# schema.net
KiCad netlist of a schematic drawn in EAGLE
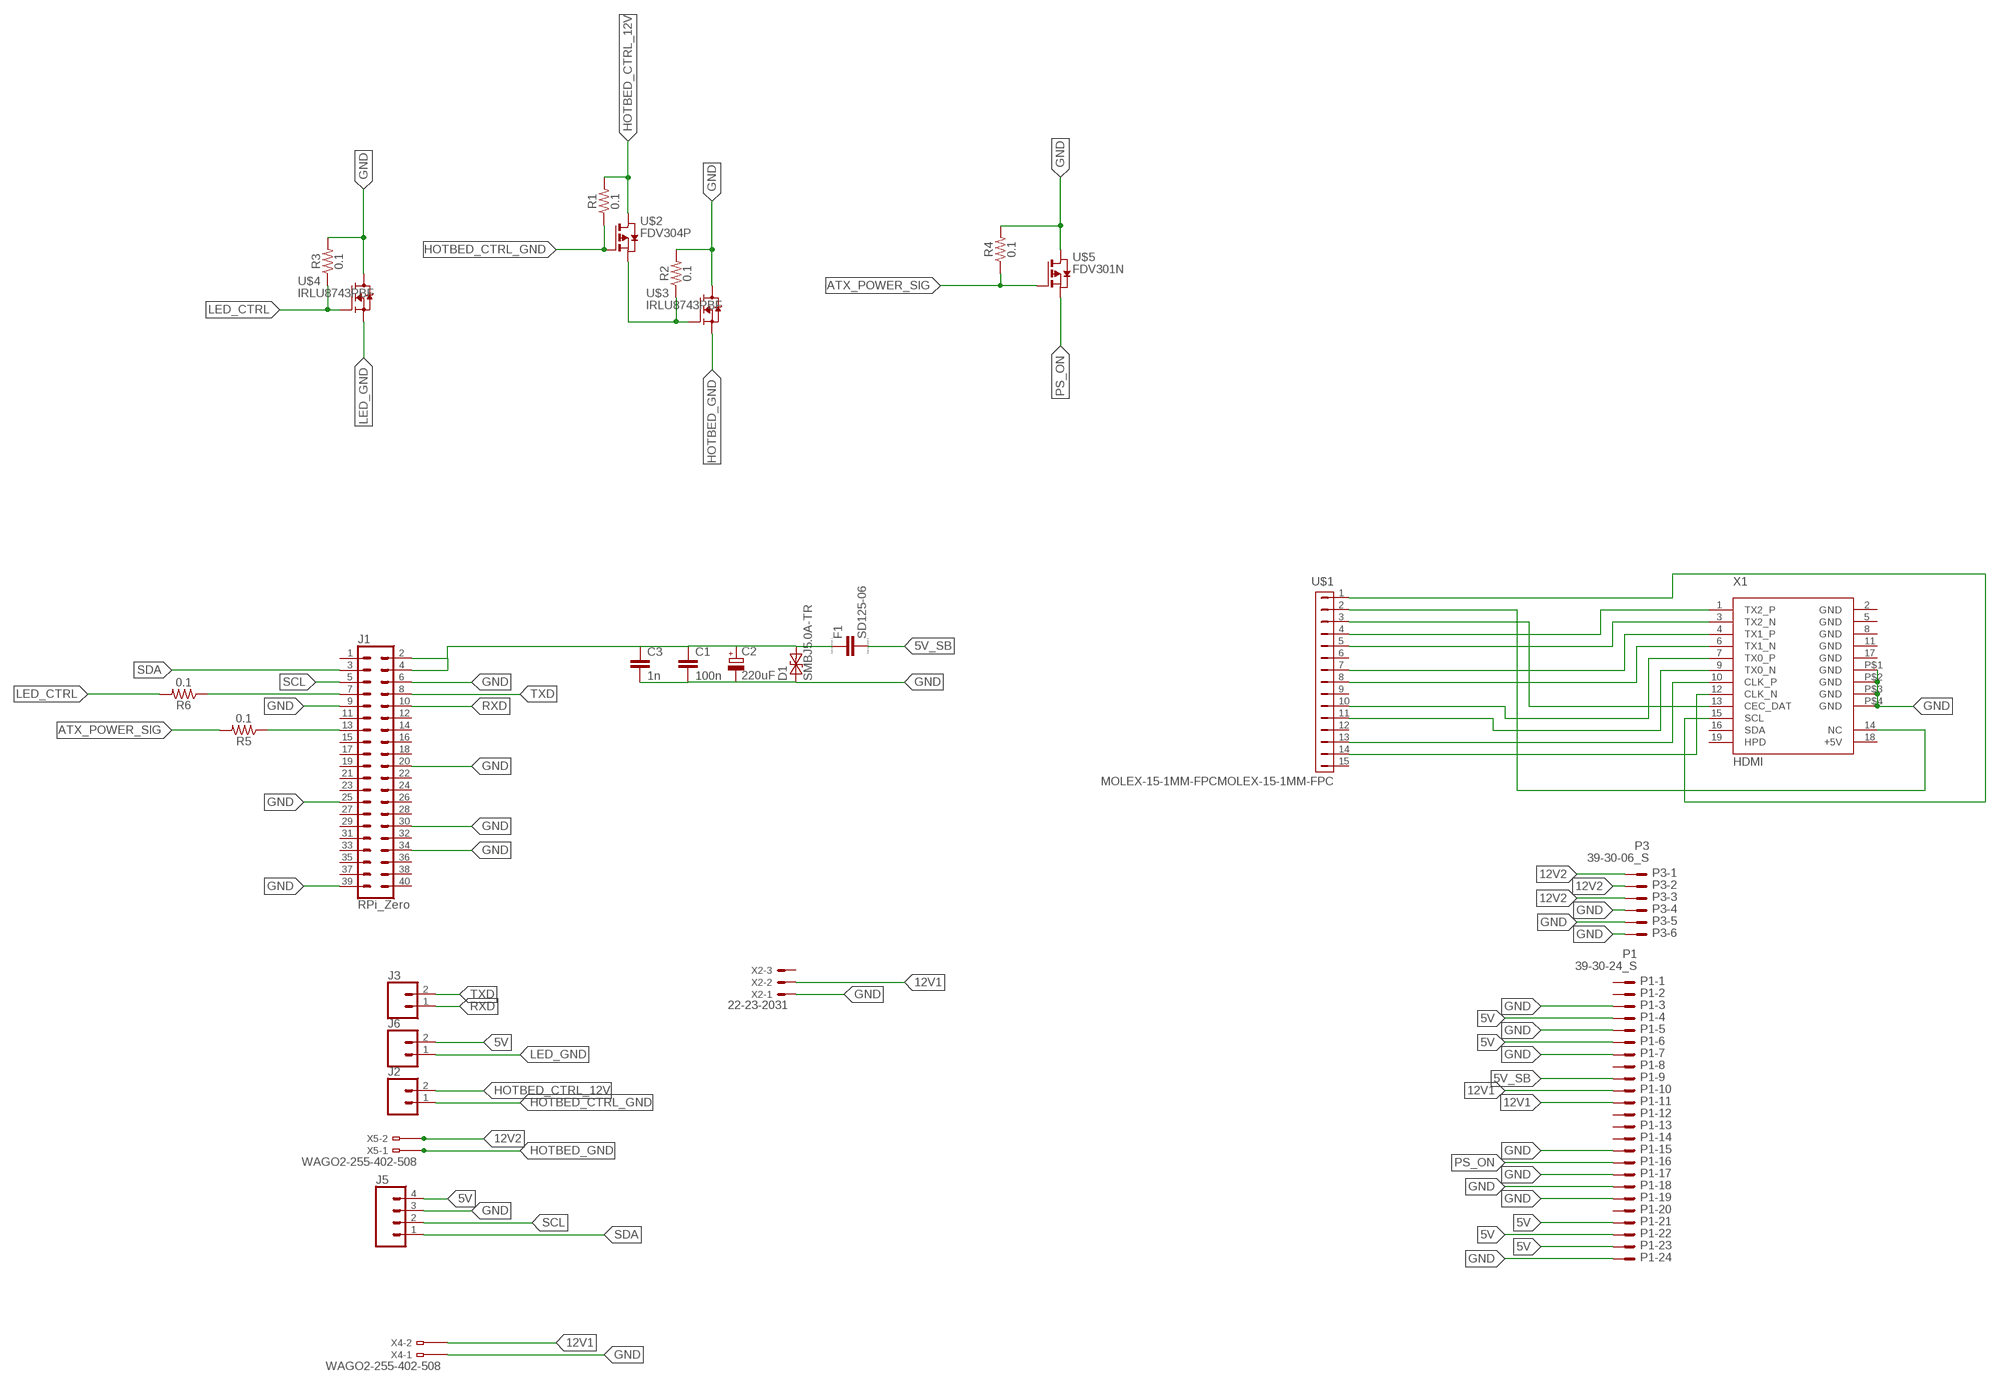
[diagram p0: schematic, sheet 1]

(export (version "E")
  (design (tool "Eeschema 10.0.6"))
  (components
    (comp (ref "C1")
      (value "100n")
      (footprint "eagle-import:C1206")
      (libsource (lib "eagle-import") (part "C-EUC1206"))
    )
    (comp (ref "C2")
      (value "220uF")
      (footprint "eagle-import:SMC_E")
      (libsource (lib "eagle-import") (part "CPOL-EUSMCE"))
    )
    (comp (ref "C3")
      (value "1n")
      (footprint "eagle-import:C1206")
      (libsource (lib "eagle-import") (part "C-EUC1206"))
    )
    (comp (ref "D1")
      (value "SMBJ5.0A-TR")
      (footprint "eagle-import:SMB")
      (libsource (lib "eagle-import") (part "P6SMBCA_"))
    )
    (comp (ref "F1")
      (value "SD125-06")
      (footprint "eagle-import:C1812")
      (libsource (lib "eagle-import") (part "CC1812"))
    )
    (comp (ref "J1")
      (value "RPi_Zero")
      (footprint "eagle-import:2X20")
      (libsource (lib "eagle-import") (part "CONN_20X2"))
    )
    (comp (ref "J2")
      (value "CONN_02")
      (footprint "eagle-import:1X02")
      (libsource (lib "eagle-import") (part "CONN_02"))
    )
    (comp (ref "J3")
      (value "CONN_02")
      (footprint "eagle-import:1X02")
      (libsource (lib "eagle-import") (part "CONN_02"))
    )
    (comp (ref "J5")
      (value "CONN_04")
      (footprint "eagle-import:1X04")
      (libsource (lib "eagle-import") (part "CONN_04"))
    )
    (comp (ref "J6")
      (value "CONN_025MM")
      (footprint "eagle-import:SCREWTERMINAL-5MM-2")
      (libsource (lib "eagle-import") (part "CONN_025MM"))
    )
    (comp (ref "P1")
      (value "39-30-24_S")
      (footprint "eagle-import:39-30-_24_")
      (libsource (lib "eagle-import") (part "39-30-?24?_S"))
    )
    (comp (ref "P3")
      (value "39-30-06_S")
      (footprint "eagle-import:39-30-_06_")
      (libsource (lib "eagle-import") (part "39-30-?06?_S"))
    )
    (comp (ref "R1")
      (value "0.1")
      (footprint "eagle-import:1210")
      (libsource (lib "eagle-import") (part "0.1OHM-1210-1/2W-1%"))
    )
    (comp (ref "R2")
      (value "0.1")
      (footprint "eagle-import:1210")
      (libsource (lib "eagle-import") (part "0.1OHM-1210-1/2W-1%"))
    )
    (comp (ref "R3")
      (value "0.1")
      (footprint "eagle-import:1210")
      (libsource (lib "eagle-import") (part "0.1OHM-1210-1/2W-1%"))
    )
    (comp (ref "R4")
      (value "0.1")
      (footprint "eagle-import:1210")
      (libsource (lib "eagle-import") (part "0.1OHM-1210-1/2W-1%"))
    )
    (comp (ref "R5")
      (value "0.1")
      (footprint "eagle-import:1210")
      (libsource (lib "eagle-import") (part "0.1OHM-1210-1/2W-1%"))
    )
    (comp (ref "R6")
      (value "0.1")
      (footprint "eagle-import:1210")
      (libsource (lib "eagle-import") (part "0.1OHM-1210-1/2W-1%"))
    )
    (comp (ref "U$1")
      (value "MOLEX-15-1MM-FPCMOLEX-15-1MM-FPC")
      (footprint "eagle-import:FH12-15S-1SH")
      (libsource (lib "eagle-import") (part "MOLEX-15-1MM-FPCMOLEX-15-1MM-FPC"))
    )
    (comp (ref "U$2")
      (value "FDV304P")
      (footprint "eagle-import:SOT-23")
      (libsource (lib "eagle-import") (part "FDV304P"))
    )
    (comp (ref "U$3")
      (value "IRLU8743PBF")
      (footprint "eagle-import:TO-251AA")
      (libsource (lib "eagle-import") (part "IRLU8743PBF"))
    )
    (comp (ref "U$4")
      (value "IRLU8743PBF")
      (footprint "eagle-import:TO-251AA")
      (libsource (lib "eagle-import") (part "IRLU8743PBF"))
    )
    (comp (ref "U$5")
      (value "FDV301N")
      (footprint "eagle-import:SOT-23")
      (libsource (lib "eagle-import") (part "FDV304P"))
    )
    (comp (ref "X1")
      (value "HDMI")
      (footprint "eagle-import:HDMI")
      (libsource (lib "eagle-import") (part "HDMI"))
    )
    (comp (ref "X2")
      (value "22-23-2031")
      (footprint "eagle-import:22-23-2031")
      (fields (field (name "MF") "MOLEX"))
      (libsource (lib "eagle-import") (part "22-23-2031"))
    )
    (comp (ref "X4")
      (value "WAGO2-255-402-508")
      (footprint "eagle-import:255-402-508")
      (libsource (lib "eagle-import") (part "WAGO2-255-402-508"))
    )
    (comp (ref "X5")
      (value "WAGO2-255-402-508")
      (footprint "eagle-import:255-402-508")
      (libsource (lib "eagle-import") (part "WAGO2-255-402-508"))
    )
  )
  (nets
    (net (code "1") (name "5V") (class "Default")
      (node (ref "J5") (pin "4") (pinfunction "4_4") (pintype "passive"))
      (node (ref "J6") (pin "2") (pinfunction "2_2") (pintype "passive"))
      (node (ref "P1") (pin "21") (pinfunction "P_21") (pintype "passive"))
      (node (ref "P1") (pin "22") (pinfunction "P_22") (pintype "passive"))
      (node (ref "P1") (pin "23") (pinfunction "P_23") (pintype "passive"))
      (node (ref "P1") (pin "4") (pinfunction "P_4") (pintype "passive"))
      (node (ref "P1") (pin "6") (pinfunction "P_6") (pintype "passive"))
    )
    (net (code "2") (name "5V_SB") (class "Default")
      (node (ref "F1") (pin "2") (pinfunction "2_2") (pintype "passive"))
      (node (ref "P1") (pin "9") (pinfunction "P_9") (pintype "passive"))
    )
    (net (code "3") (name "12V1") (class "Default")
      (node (ref "P1") (pin "10") (pinfunction "P_10") (pintype "passive"))
      (node (ref "P1") (pin "11") (pinfunction "P_11") (pintype "passive"))
      (node (ref "X2") (pin "2") (pinfunction "S_2") (pintype "passive"))
      (node (ref "X4") (pin "B2") (pinfunction "B1_B2") (pintype "passive"))
    )
    (net (code "4") (name "12V2") (class "Default")
      (node (ref "P3") (pin "1") (pinfunction "P_1") (pintype "passive"))
      (node (ref "P3") (pin "2") (pinfunction "P_2") (pintype "passive"))
      (node (ref "P3") (pin "3") (pinfunction "P_3") (pintype "passive"))
      (node (ref "X5") (pin "B2") (pinfunction "B1_B2") (pintype "passive"))
    )
    (net (code "5") (name "ATX_POWER_SIG") (class "Default")
      (node (ref "R4") (pin "1") (pinfunction "1_1") (pintype "passive"))
      (node (ref "R5") (pin "2") (pinfunction "2_2") (pintype "passive"))
      (node (ref "U$5") (pin "2") (pinfunction "G_2") (pintype "passive"))
    )
    (net (code "6") (name "GND") (class "Default")
      (node (ref "C1") (pin "2") (pinfunction "2_2") (pintype "passive"))
      (node (ref "C2") (pin "-") (pinfunction "-_-") (pintype "passive"))
      (node (ref "C3") (pin "2") (pinfunction "2_2") (pintype "passive"))
      (node (ref "D1") (pin "1") (pinfunction "1_1") (pintype "passive"))
      (node (ref "J1") (pin "20") (pinfunction "20_20") (pintype "passive"))
      (node (ref "J1") (pin "25") (pinfunction "25_25") (pintype "passive"))
      (node (ref "J1") (pin "30") (pinfunction "30_30") (pintype "passive"))
      (node (ref "J1") (pin "34") (pinfunction "34_34") (pintype "passive"))
      (node (ref "J1") (pin "39") (pinfunction "39_39") (pintype "passive"))
      (node (ref "J1") (pin "6") (pinfunction "6_6") (pintype "passive"))
      (node (ref "J1") (pin "9") (pinfunction "9_9") (pintype "passive"))
      (node (ref "J5") (pin "3") (pinfunction "3_3") (pintype "passive"))
      (node (ref "P1") (pin "15") (pinfunction "P_15") (pintype "passive"))
      (node (ref "P1") (pin "17") (pinfunction "P_17") (pintype "passive"))
      (node (ref "P1") (pin "18") (pinfunction "P_18") (pintype "passive"))
      (node (ref "P1") (pin "19") (pinfunction "P_19") (pintype "passive"))
      (node (ref "P1") (pin "24") (pinfunction "P_24") (pintype "passive"))
      (node (ref "P1") (pin "3") (pinfunction "P_3") (pintype "passive"))
      (node (ref "P1") (pin "5") (pinfunction "P_5") (pintype "passive"))
      (node (ref "P1") (pin "7") (pinfunction "P_7") (pintype "passive"))
      (node (ref "P3") (pin "4") (pinfunction "P_4") (pintype "passive"))
      (node (ref "P3") (pin "5") (pinfunction "P_5") (pintype "passive"))
      (node (ref "P3") (pin "6") (pinfunction "P_6") (pintype "passive"))
      (node (ref "R2") (pin "2") (pinfunction "2_2") (pintype "passive"))
      (node (ref "R3") (pin "2") (pinfunction "2_2") (pintype "passive"))
      (node (ref "R4") (pin "2") (pinfunction "2_2") (pintype "passive"))
      (node (ref "U$3") (pin "2") (pinfunction "D_2") (pintype "passive"))
      (node (ref "U$3") (pin "4") (pinfunction "D_4") (pintype "passive"))
      (node (ref "U$4") (pin "2") (pinfunction "D_2") (pintype "passive"))
      (node (ref "U$4") (pin "4") (pinfunction "D_4") (pintype "passive"))
      (node (ref "U$5") (pin "1") (pinfunction "D_1") (pintype "passive"))
      (node (ref "X1") (pin "P$1") (pinfunction "GND_P$1") (pintype "bidirectional"))
      (node (ref "X1") (pin "P$2") (pinfunction "GND_P$2") (pintype "bidirectional"))
      (node (ref "X1") (pin "P$3") (pinfunction "GND_P$3") (pintype "bidirectional"))
      (node (ref "X1") (pin "P$4") (pinfunction "GND_P$4") (pintype "bidirectional"))
      (node (ref "X2") (pin "1") (pinfunction "S_1") (pintype "passive"))
      (node (ref "X4") (pin "B1") (pinfunction "B1_B1") (pintype "passive"))
    )
    (net (code "7") (name "HOTBED_CTRL_12V") (class "Default")
      (node (ref "J2") (pin "2") (pinfunction "2_2") (pintype "passive"))
      (node (ref "R1") (pin "2") (pinfunction "2_2") (pintype "passive"))
      (node (ref "U$2") (pin "1") (pinfunction "D_1") (pintype "passive"))
    )
    (net (code "8") (name "HOTBED_CTRL_GND") (class "Default")
      (node (ref "J2") (pin "1") (pinfunction "1_1") (pintype "passive"))
      (node (ref "R1") (pin "1") (pinfunction "1_1") (pintype "passive"))
      (node (ref "U$2") (pin "2") (pinfunction "G_2") (pintype "passive"))
    )
    (net (code "9") (name "HOTBED_GND") (class "Default")
      (node (ref "U$3") (pin "3") (pinfunction "S_3") (pintype "passive"))
      (node (ref "X5") (pin "B1") (pinfunction "B1_B1") (pintype "passive"))
    )
    (net (code "10") (name "LED_CTRL") (class "Default")
      (node (ref "R3") (pin "1") (pinfunction "1_1") (pintype "passive"))
      (node (ref "R6") (pin "2") (pinfunction "2_2") (pintype "passive"))
      (node (ref "U$4") (pin "1") (pinfunction "G_1") (pintype "passive"))
    )
    (net (code "11") (name "LED_GND") (class "Default")
      (node (ref "J6") (pin "1") (pinfunction "1_1") (pintype "passive"))
      (node (ref "U$4") (pin "3") (pinfunction "S_3") (pintype "passive"))
    )
    (net (code "12") (name "Net-(C1-Pad1)") (class "Default")
      (node (ref "C1") (pin "1") (pinfunction "1_1") (pintype "passive"))
      (node (ref "C2") (pin "+") (pinfunction "+_+") (pintype "passive"))
      (node (ref "C3") (pin "1") (pinfunction "1_1") (pintype "passive"))
      (node (ref "D1") (pin "2") (pinfunction "2_2") (pintype "passive"))
      (node (ref "F1") (pin "1") (pinfunction "1_1") (pintype "passive"))
      (node (ref "J1") (pin "2") (pinfunction "2_2") (pintype "passive"))
      (node (ref "J1") (pin "4") (pinfunction "4_4") (pintype "passive"))
    )
    (net (code "13") (name "Net-(J1-Pad7)") (class "Default")
      (node (ref "J1") (pin "7") (pinfunction "7_7") (pintype "passive"))
      (node (ref "R6") (pin "1") (pinfunction "1_1") (pintype "passive"))
    )
    (net (code "14") (name "Net-(J1-Pad13)") (class "Default")
      (node (ref "J1") (pin "13") (pinfunction "13_13") (pintype "passive"))
      (node (ref "R5") (pin "1") (pinfunction "1_1") (pintype "passive"))
    )
    (net (code "15") (name "Net-(U$2-S)") (class "Default")
      (node (ref "R2") (pin "1") (pinfunction "1_1") (pintype "passive"))
      (node (ref "U$2") (pin "3") (pinfunction "S_3") (pintype "passive"))
      (node (ref "U$3") (pin "1") (pinfunction "G_1") (pintype "passive"))
    )
    (net (code "16") (name "Net-(X1-CEC_DAT)") (class "Default")
      (node (ref "U$1") (pin "3") (pinfunction "3_3") (pintype "passive"))
      (node (ref "X1") (pin "13") (pinfunction "CEC_DAT_13") (pintype "bidirectional"))
    )
    (net (code "17") (name "Net-(X1-CLK_N)") (class "Default")
      (node (ref "U$1") (pin "14") (pinfunction "14_14") (pintype "passive"))
      (node (ref "X1") (pin "12") (pinfunction "CLK_N_12") (pintype "bidirectional"))
    )
    (net (code "18") (name "Net-(X1-CLK_P)") (class "Default")
      (node (ref "U$1") (pin "13") (pinfunction "13_13") (pintype "passive"))
      (node (ref "X1") (pin "10") (pinfunction "CLK_P_10") (pintype "bidirectional"))
    )
    (net (code "19") (name "Net-(X1-NC)") (class "Default")
      (node (ref "U$1") (pin "2") (pinfunction "2_2") (pintype "passive"))
      (node (ref "X1") (pin "14") (pinfunction "NC_14") (pintype "bidirectional"))
    )
    (net (code "20") (name "Net-(X1-SCL)") (class "Default")
      (node (ref "U$1") (pin "1") (pinfunction "1_1") (pintype "passive"))
      (node (ref "X1") (pin "15") (pinfunction "SCL_15") (pintype "bidirectional"))
    )
    (net (code "21") (name "Net-(X1-TX0_N)") (class "Default")
      (node (ref "U$1") (pin "11") (pinfunction "11_11") (pintype "passive"))
      (node (ref "X1") (pin "9") (pinfunction "TX0_N_9") (pintype "bidirectional"))
    )
    (net (code "22") (name "Net-(X1-TX0_P)") (class "Default")
      (node (ref "U$1") (pin "10") (pinfunction "10_10") (pintype "passive"))
      (node (ref "X1") (pin "7") (pinfunction "TX0_P_7") (pintype "bidirectional"))
    )
    (net (code "23") (name "Net-(X1-TX1_N)") (class "Default")
      (node (ref "U$1") (pin "8") (pinfunction "8_8") (pintype "passive"))
      (node (ref "X1") (pin "6") (pinfunction "TX1_N_6") (pintype "bidirectional"))
    )
    (net (code "24") (name "Net-(X1-TX1_P)") (class "Default")
      (node (ref "U$1") (pin "7") (pinfunction "7_7") (pintype "passive"))
      (node (ref "X1") (pin "4") (pinfunction "TX1_P_4") (pintype "bidirectional"))
    )
    (net (code "25") (name "Net-(X1-TX2_N)") (class "Default")
      (node (ref "U$1") (pin "5") (pinfunction "5_5") (pintype "passive"))
      (node (ref "X1") (pin "3") (pinfunction "TX2_N_3") (pintype "bidirectional"))
    )
    (net (code "26") (name "Net-(X1-TX2_P)") (class "Default")
      (node (ref "U$1") (pin "4") (pinfunction "4_4") (pintype "passive"))
      (node (ref "X1") (pin "1") (pinfunction "TX2_P_1") (pintype "bidirectional"))
    )
    (net (code "27") (name "PS_ON") (class "Default")
      (node (ref "P1") (pin "16") (pinfunction "P_16") (pintype "passive"))
      (node (ref "U$5") (pin "3") (pinfunction "S_3") (pintype "passive"))
    )
    (net (code "28") (name "RXD") (class "Default")
      (node (ref "J1") (pin "10") (pinfunction "10_10") (pintype "passive"))
      (node (ref "J3") (pin "1") (pinfunction "1_1") (pintype "passive"))
    )
    (net (code "29") (name "SCL") (class "Default")
      (node (ref "J1") (pin "5") (pinfunction "5_5") (pintype "passive"))
      (node (ref "J5") (pin "2") (pinfunction "2_2") (pintype "passive"))
    )
    (net (code "30") (name "SDA") (class "Default")
      (node (ref "J1") (pin "3") (pinfunction "3_3") (pintype "passive"))
      (node (ref "J5") (pin "1") (pinfunction "1_1") (pintype "passive"))
    )
    (net (code "31") (name "TXD") (class "Default")
      (node (ref "J1") (pin "8") (pinfunction "8_8") (pintype "passive"))
      (node (ref "J3") (pin "2") (pinfunction "2_2") (pintype "passive"))
    )
    (net (code "32") (name "unconnected-(J1-Pad1)") (class "Default")
      (node (ref "J1") (pin "1") (pinfunction "1_1") (pintype "passive"))
    )
    (net (code "33") (name "unconnected-(J1-Pad11)") (class "Default")
      (node (ref "J1") (pin "11") (pinfunction "11_11") (pintype "passive"))
    )
    (net (code "34") (name "unconnected-(J1-Pad12)") (class "Default")
      (node (ref "J1") (pin "12") (pinfunction "12_12") (pintype "passive"))
    )
    (net (code "35") (name "unconnected-(J1-Pad14)") (class "Default")
      (node (ref "J1") (pin "14") (pinfunction "14_14") (pintype "passive"))
    )
    (net (code "36") (name "unconnected-(J1-Pad15)") (class "Default")
      (node (ref "J1") (pin "15") (pinfunction "15_15") (pintype "passive"))
    )
    (net (code "37") (name "unconnected-(J1-Pad16)") (class "Default")
      (node (ref "J1") (pin "16") (pinfunction "16_16") (pintype "passive"))
    )
    (net (code "38") (name "unconnected-(J1-Pad17)") (class "Default")
      (node (ref "J1") (pin "17") (pinfunction "17_17") (pintype "passive"))
    )
    (net (code "39") (name "unconnected-(J1-Pad18)") (class "Default")
      (node (ref "J1") (pin "18") (pinfunction "18_18") (pintype "passive"))
    )
    (net (code "40") (name "unconnected-(J1-Pad19)") (class "Default")
      (node (ref "J1") (pin "19") (pinfunction "19_19") (pintype "passive"))
    )
    (net (code "41") (name "unconnected-(J1-Pad21)") (class "Default")
      (node (ref "J1") (pin "21") (pinfunction "21_21") (pintype "passive"))
    )
    (net (code "42") (name "unconnected-(J1-Pad22)") (class "Default")
      (node (ref "J1") (pin "22") (pinfunction "22_22") (pintype "passive"))
    )
    (net (code "43") (name "unconnected-(J1-Pad23)") (class "Default")
      (node (ref "J1") (pin "23") (pinfunction "23_23") (pintype "passive"))
    )
    (net (code "44") (name "unconnected-(J1-Pad24)") (class "Default")
      (node (ref "J1") (pin "24") (pinfunction "24_24") (pintype "passive"))
    )
    (net (code "45") (name "unconnected-(J1-Pad26)") (class "Default")
      (node (ref "J1") (pin "26") (pinfunction "26_26") (pintype "passive"))
    )
    (net (code "46") (name "unconnected-(J1-Pad27)") (class "Default")
      (node (ref "J1") (pin "27") (pinfunction "27_27") (pintype "passive"))
    )
    (net (code "47") (name "unconnected-(J1-Pad28)") (class "Default")
      (node (ref "J1") (pin "28") (pinfunction "28_28") (pintype "passive"))
    )
    (net (code "48") (name "unconnected-(J1-Pad29)") (class "Default")
      (node (ref "J1") (pin "29") (pinfunction "29_29") (pintype "passive"))
    )
    (net (code "49") (name "unconnected-(J1-Pad31)") (class "Default")
      (node (ref "J1") (pin "31") (pinfunction "31_31") (pintype "passive"))
    )
    (net (code "50") (name "unconnected-(J1-Pad32)") (class "Default")
      (node (ref "J1") (pin "32") (pinfunction "32_32") (pintype "passive"))
    )
    (net (code "51") (name "unconnected-(J1-Pad33)") (class "Default")
      (node (ref "J1") (pin "33") (pinfunction "33_33") (pintype "passive"))
    )
    (net (code "52") (name "unconnected-(J1-Pad35)") (class "Default")
      (node (ref "J1") (pin "35") (pinfunction "35_35") (pintype "passive"))
    )
    (net (code "53") (name "unconnected-(J1-Pad36)") (class "Default")
      (node (ref "J1") (pin "36") (pinfunction "36_36") (pintype "passive"))
    )
    (net (code "54") (name "unconnected-(J1-Pad37)") (class "Default")
      (node (ref "J1") (pin "37") (pinfunction "37_37") (pintype "passive"))
    )
    (net (code "55") (name "unconnected-(J1-Pad38)") (class "Default")
      (node (ref "J1") (pin "38") (pinfunction "38_38") (pintype "passive"))
    )
    (net (code "56") (name "unconnected-(J1-Pad40)") (class "Default")
      (node (ref "J1") (pin "40") (pinfunction "40_40") (pintype "passive"))
    )
    (net (code "57") (name "unconnected-(P1A-P-Pad1)") (class "Default")
      (node (ref "P1") (pin "1") (pinfunction "P_1") (pintype "passive"))
    )
    (net (code "58") (name "unconnected-(P1D-P-Pad12)") (class "Default")
      (node (ref "P1") (pin "12") (pinfunction "P_12") (pintype "passive"))
    )
    (net (code "59") (name "unconnected-(P1E-P-Pad13)") (class "Default")
      (node (ref "P1") (pin "13") (pinfunction "P_13") (pintype "passive"))
    )
    (net (code "60") (name "unconnected-(P1F-P-Pad14)") (class "Default")
      (node (ref "P1") (pin "14") (pinfunction "P_14") (pintype "passive"))
    )
    (net (code "61") (name "unconnected-(P1L-P-Pad2)") (class "Default")
      (node (ref "P1") (pin "2") (pinfunction "P_2") (pintype "passive"))
    )
    (net (code "62") (name "unconnected-(P1M-P-Pad20)") (class "Default")
      (node (ref "P1") (pin "20") (pinfunction "P_20") (pintype "passive"))
    )
    (net (code "63") (name "unconnected-(P1W-P-Pad8)") (class "Default")
      (node (ref "P1") (pin "8") (pinfunction "P_8") (pintype "passive"))
    )
    (net (code "64") (name "unconnected-(U$1-Pad6)") (class "Default")
      (node (ref "U$1") (pin "6") (pinfunction "6_6") (pintype "passive"))
    )
    (net (code "65") (name "unconnected-(U$1-Pad9)") (class "Default")
      (node (ref "U$1") (pin "9") (pinfunction "9_9") (pintype "passive"))
    )
    (net (code "66") (name "unconnected-(U$1-Pad12)") (class "Default")
      (node (ref "U$1") (pin "12") (pinfunction "12_12") (pintype "passive"))
    )
    (net (code "67") (name "unconnected-(U$1-Pad15)") (class "Default")
      (node (ref "U$1") (pin "15") (pinfunction "15_15") (pintype "passive"))
    )
    (net (code "68") (name "unconnected-(X1-+5V-Pad18)") (class "Default")
      (node (ref "X1") (pin "18") (pinfunction "+5V_18") (pintype "bidirectional"))
    )
    (net (code "69") (name "unconnected-(X1-GND-Pad2)") (class "Default")
      (node (ref "X1") (pin "2") (pinfunction "GND_2") (pintype "bidirectional"))
    )
    (net (code "70") (name "unconnected-(X1-GND-Pad5)") (class "Default")
      (node (ref "X1") (pin "5") (pinfunction "GND_5") (pintype "bidirectional"))
    )
    (net (code "71") (name "unconnected-(X1-GND-Pad8)") (class "Default")
      (node (ref "X1") (pin "8") (pinfunction "GND_8") (pintype "bidirectional"))
    )
    (net (code "72") (name "unconnected-(X1-GND-Pad11)") (class "Default")
      (node (ref "X1") (pin "11") (pinfunction "GND_11") (pintype "bidirectional"))
    )
    (net (code "73") (name "unconnected-(X1-GND-Pad17)") (class "Default")
      (node (ref "X1") (pin "17") (pinfunction "GND_17") (pintype "bidirectional"))
    )
    (net (code "74") (name "unconnected-(X1-HPD-Pad19)") (class "Default")
      (node (ref "X1") (pin "19") (pinfunction "HPD_19") (pintype "bidirectional"))
    )
    (net (code "75") (name "unconnected-(X1-SDA-Pad16)") (class "Default")
      (node (ref "X1") (pin "16") (pinfunction "SDA_16") (pintype "bidirectional"))
    )
    (net (code "76") (name "unconnected-(X2C-S-Pad3)") (class "Default")
      (node (ref "X2") (pin "3") (pinfunction "S_3") (pintype "passive"))
    )
    (net (code "77") (name "unconnected-(X4-PadA1)") (class "Default")
      (node (ref "X4") (pin "A1") (pinfunction "A1_A1") (pintype "passive"))
    )
    (net (code "78") (name "unconnected-(X4B-A1-PadA2)") (class "Default")
      (node (ref "X4") (pin "A2") (pinfunction "A1_A2") (pintype "passive"))
    )
    (net (code "79") (name "unconnected-(X5-PadA1)") (class "Default")
      (node (ref "X5") (pin "A1") (pinfunction "A1_A1") (pintype "passive"))
    )
    (net (code "80") (name "unconnected-(X5B-A1-PadA2)") (class "Default")
      (node (ref "X5") (pin "A2") (pinfunction "A1_A2") (pintype "passive"))
    )
  )
)
